# CX1086_Sheet1.net
KiCad netlist of a schematic drawn in Altium Designer
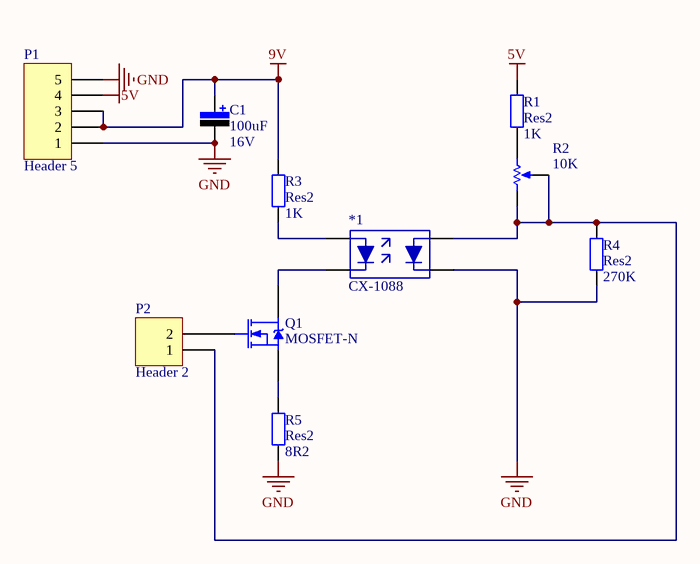
[diagram p0: CX1086_Sheet1.SchDoc]

(export (version "E")
  (design (tool "Eeschema 10.0.6"))
  (components
    (comp (ref "*1") (value "CX-1088") (footprint "CX-1088") (libsource (lib "fszhang") (part "CX-1088")))
    (comp (ref "C1")
      (value "100uF")
      (footprint "C-RB-8")
      (description "极性电解电容")
      (fields
        (field (name "VOL") "16V")
        (field (name "Comment") "Cap Pol")
        (field (name "PUBLISHER") "Altium Limited")
      )
      (libsource (lib "fszhang") (part "Cap Pol"))
    )
    (comp (ref "P1")
      (value "Header 5")
      (footprint "HDR1X5")
      (description "Header, 5-Pin")
      (fields (field (name "PUBLISHER") "Altium Limited"))
      (libsource (lib "Miscellaneous Connectors") (part "Header 5"))
    )
    (comp (ref "P2")
      (value "Header 2")
      (footprint "HDR1X2")
      (description "Header, 2-Pin")
      (fields (field (name "PUBLISHER") "Altium Limited"))
      (libsource (lib "Miscellaneous Connectors") (part "Header 2"))
    )
    (comp (ref "Q1")
      (value "MOSFET-N")
      (footprint "TO-220AB")
      (description "N-Channel MOSFET")
      (fields (field (name "PUBLISHER") "Altium Limited"))
      (libsource (lib "fszhang") (part "MOSFET-N"))
    )
    (comp (ref "R1")
      (value "Res2")
      (footprint "AXIAL-0.4")
      (description "Resistor")
      (fields (field (name "ALTIUM_VALUE") "1K") (field (name "PUBLISHER") "Altium Limited"))
      (libsource (lib "Miscellaneous Devices") (part "Res2"))
    )
    (comp (ref "R2")
      (value "10K")
      (footprint "VR_A1")
      (description "精密可调电阻")
      (fields (field (name "Comment") "RES-RPot") (field (name "PUBLISHER") "Altium Limited"))
      (libsource (lib "fszhang") (part "RES-RPot"))
    )
    (comp (ref "R3")
      (value "Res2")
      (footprint "AXIAL-0.4")
      (description "Resistor")
      (fields (field (name "ALTIUM_VALUE") "1K") (field (name "PUBLISHER") "Altium Limited"))
      (libsource (lib "Miscellaneous Devices") (part "Res2"))
    )
    (comp (ref "R4")
      (value "Res2")
      (footprint "AXIAL-0.4")
      (description "Resistor")
      (fields (field (name "ALTIUM_VALUE") "270K") (field (name "PUBLISHER") "Altium Limited"))
      (libsource (lib "Miscellaneous Devices") (part "Res2"))
    )
    (comp (ref "R5")
      (value "Res2")
      (footprint "AXIAL-0.4")
      (description "Resistor")
      (fields (field (name "ALTIUM_VALUE") "8R2") (field (name "PUBLISHER") "Altium Limited"))
      (libsource (lib "Miscellaneous Devices") (part "Res2"))
    )
  )
  (nets
    (net (code "1") (name "5V") (class "Default")
      (node (ref "P1") (pin "4") (pinfunction "4_4") (pintype "passive"))
      (node (ref "R1") (pin "2") (pinfunction "2_2") (pintype "passive"))
    )
    (net (code "2") (name "9V") (class "Default")
      (node (ref "C1") (pin "1") (pinfunction "1_1") (pintype "passive"))
      (node (ref "P1") (pin "2") (pinfunction "2_2") (pintype "passive"))
      (node (ref "P1") (pin "3") (pinfunction "3_3") (pintype "passive"))
      (node (ref "R3") (pin "2") (pinfunction "2_2") (pintype "passive"))
    )
    (net (code "3") (name "GND") (class "Default")
      (node (ref "*1") (pin "2") (pinfunction "PD-K_2") (pintype "passive"))
      (node (ref "C1") (pin "2") (pinfunction "2_2") (pintype "passive"))
      (node (ref "P1") (pin "1") (pinfunction "1_1") (pintype "passive"))
      (node (ref "P1") (pin "5") (pinfunction "5_5") (pintype "passive"))
      (node (ref "R4") (pin "1") (pinfunction "1_1") (pintype "passive"))
      (node (ref "R5") (pin "1") (pinfunction "1_1") (pintype "passive"))
    )
    (net (code "4") (name "Net-(*1-IRED-A)") (class "Default")
      (node (ref "*1") (pin "3") (pinfunction "IRED-A_3") (pintype "passive"))
      (node (ref "R3") (pin "1") (pinfunction "1_1") (pintype "passive"))
    )
    (net (code "5") (name "Net-(*1-IRED-K)") (class "Default")
      (node (ref "*1") (pin "4") (pinfunction "IRED-K_4") (pintype "passive"))
      (node (ref "Q1") (pin "D") (pinfunction "D_D") (pintype "passive"))
    )
    (net (code "6") (name "Net-(*1-PD-A)") (class "Default")
      (node (ref "*1") (pin "1") (pinfunction "PD-A_1") (pintype "passive"))
      (node (ref "P2") (pin "1") (pinfunction "1_1") (pintype "passive"))
      (node (ref "R2") (pin "1") (pinfunction "TOP_1") (pintype "passive"))
      (node (ref "R2") (pin "2") (pinfunction "TAP_2") (pintype "passive"))
      (node (ref "R4") (pin "2") (pinfunction "2_2") (pintype "passive"))
    )
    (net (code "7") (name "Net-(P2-Pad2)") (class "Default")
      (node (ref "P2") (pin "2") (pinfunction "2_2") (pintype "passive"))
      (node (ref "Q1") (pin "G") (pinfunction "G_G") (pintype "passive"))
    )
    (net (code "8") (name "Net-(Q1-PadS)") (class "Default")
      (node (ref "Q1") (pin "S") (pinfunction "S_S") (pintype "passive"))
      (node (ref "R5") (pin "2") (pinfunction "2_2") (pintype "passive"))
    )
    (net (code "9") (name "Net-(R2-BOT)") (class "Default")
      (node (ref "R1") (pin "1") (pinfunction "1_1") (pintype "passive"))
      (node (ref "R2") (pin "3") (pinfunction "BOT_3") (pintype "passive"))
    )
  )
)
